# komahub-v1_2.net
KiCad netlist of a schematic drawn in EAGLE
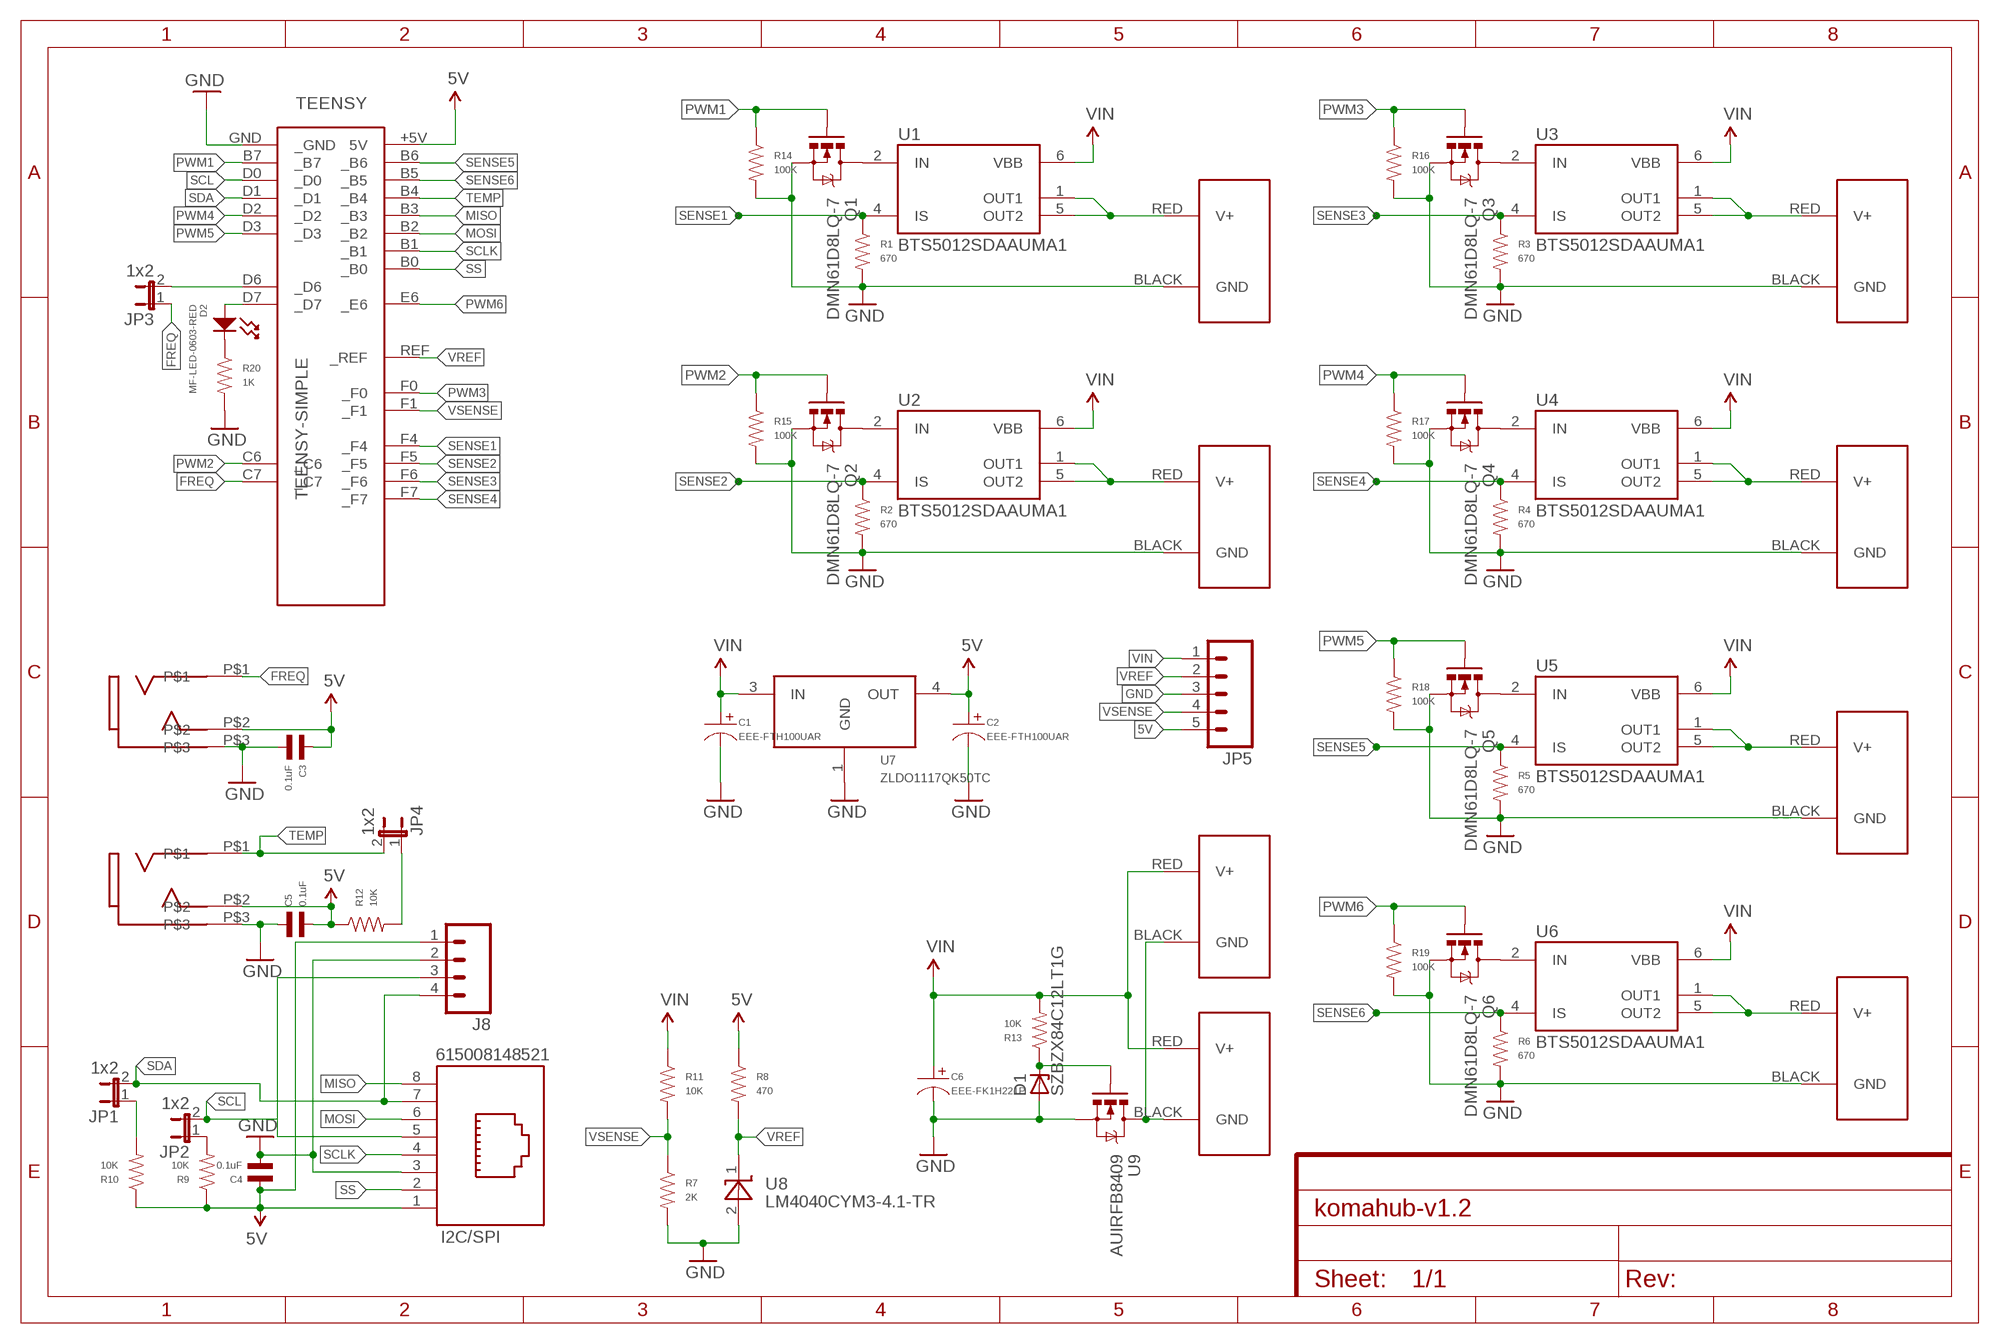
[diagram p0: schematic, sheet 1]

(export (version "E")
  (design (tool "Eeschema 10.0.6"))
  (components
    (comp (ref "C1")
      (value "EEE-FTH100UAR")
      (footprint "eagle-import:CP4MM")
      (fields (field (name "MPN") "MF-CAP-4MM-10uF"))
      (libsource (lib "eagle-import") (part "CAPACITOR_P_4MM"))
    )
    (comp (ref "C2")
      (value "EEE-FTH100UAR")
      (footprint "eagle-import:CP4MM")
      (fields (field (name "MPN") "MF-CAP-4MM-10uF"))
      (libsource (lib "eagle-import") (part "CAPACITOR_P_4MM"))
    )
    (comp (ref "C3")
      (value "0.1uF")
      (footprint "eagle-import:C0603")
      (libsource (lib "eagle-import") (part "CAPACITOR_NP_0603"))
    )
    (comp (ref "C4")
      (value "0.1uF")
      (footprint "eagle-import:C0603")
      (libsource (lib "eagle-import") (part "CAPACITOR_NP_0603"))
    )
    (comp (ref "C5")
      (value "0.1uF")
      (footprint "eagle-import:C0603")
      (libsource (lib "eagle-import") (part "CAPACITOR_NP_0603"))
    )
    (comp (ref "C6")
      (value "EEE-FK1H221P")
      (footprint "eagle-import:CP10MM")
      (fields (field (name "MPN") "EEE-FT1H221AP"))
      (libsource (lib "eagle-import") (part "CAPACITOR_P_10MM"))
    )
    (comp (ref "D1")
      (value "SZBZX84C12LT1G")
      (footprint "eagle-import:SOT23")
      (libsource (lib "eagle-import") (part "ZENER-DIODESOT23"))
    )
    (comp (ref "D2")
      (value "MF-LED-0603-RED")
      (footprint "eagle-import:LED0603")
      (fields (field (name "HOUSEPART") "YES"))
      (libsource (lib "eagle-import") (part "LED_SINGLE-0603-RED"))
    )
    (comp (ref "FREQ")
      (value "35RASMT2BHNTRX")
      (footprint "eagle-import:35RASMT2BHNTRX")
      (libsource (lib "eagle-import") (part "35RASMT2BHNTRX"))
    )
    (comp (ref "I2C/SPI")
      (value "615008148521")
      (footprint "eagle-import:615008148521")
      (libsource (lib "eagle-import") (part "615008148521"))
    )
    (comp (ref "J1")
      (value "POWERPOLE_POWER25A_HORIZONTAL_G11")
      (footprint "eagle-import:POWERPOLE_PAIR_25A_HORIZ_G11")
      (libsource (lib "eagle-import") (part "POWERPOLE_POWER25A_HORIZONTAL_G11"))
    )
    (comp (ref "J2")
      (value "POWERPOLE_POWER25A_HORIZONTAL_G11")
      (footprint "eagle-import:POWERPOLE_PAIR_25A_HORIZ_G11")
      (libsource (lib "eagle-import") (part "POWERPOLE_POWER25A_HORIZONTAL_G11"))
    )
    (comp (ref "J3")
      (value "POWERPOLE_POWER25A_HORIZONTAL_G12")
      (footprint "eagle-import:POWERPOLE_PAIR_25A_HORIZ_G12")
      (libsource (lib "eagle-import") (part "POWERPOLE_POWER25A_HORIZONTAL_G12"))
    )
    (comp (ref "J4")
      (value "POWERPOLE_POWER25A_HORIZONTAL_G12")
      (footprint "eagle-import:POWERPOLE_PAIR_25A_HORIZ_G12")
      (libsource (lib "eagle-import") (part "POWERPOLE_POWER25A_HORIZONTAL_G12"))
    )
    (comp (ref "J5")
      (value "POWERPOLE_POWER25A_HORIZONTAL_G12")
      (footprint "eagle-import:POWERPOLE_PAIR_25A_HORIZ_G12")
      (libsource (lib "eagle-import") (part "POWERPOLE_POWER25A_HORIZONTAL_G12"))
    )
    (comp (ref "J6")
      (value "POWERPOLE_POWER25A_HORIZONTAL_G11")
      (footprint "eagle-import:POWERPOLE_PAIR_25A_HORIZ_G11")
      (libsource (lib "eagle-import") (part "POWERPOLE_POWER25A_HORIZONTAL_G11"))
    )
    (comp (ref "J7")
      (value "POWERPOLE_POWER25A_HORIZONTAL_G11")
      (footprint "eagle-import:POWERPOLE_PAIR_25A_HORIZ_G11")
      (libsource (lib "eagle-import") (part "POWERPOLE_POWER25A_HORIZONTAL_G11"))
    )
    (comp (ref "J8")
      (value "M04PTH")
      (footprint "eagle-import:1X04")
      (libsource (lib "eagle-import") (part "M04PTH"))
    )
    (comp (ref "J9")
      (value "POWERPOLE_POWER25A_HORIZONTAL_G12")
      (footprint "eagle-import:POWERPOLE_PAIR_25A_HORIZ_G12")
      (libsource (lib "eagle-import") (part "POWERPOLE_POWER25A_HORIZONTAL_G12"))
    )
    (comp (ref "JP1")
      (value "1x2")
      (footprint "eagle-import:1X02")
      (libsource (lib "eagle-import") (part "JUMPER-2PTH"))
    )
    (comp (ref "JP2")
      (value "1x2")
      (footprint "eagle-import:1X02")
      (libsource (lib "eagle-import") (part "JUMPER-2PTH"))
    )
    (comp (ref "JP3")
      (value "1x2")
      (footprint "eagle-import:1X02")
      (libsource (lib "eagle-import") (part "JUMPER-2PTH"))
    )
    (comp (ref "JP4")
      (value "1x2")
      (footprint "eagle-import:1X02")
      (libsource (lib "eagle-import") (part "JUMPER-2PTH"))
    )
    (comp (ref "JP5")
      (value "M05PTH")
      (footprint "eagle-import:1X05")
      (libsource (lib "eagle-import") (part "M05PTH"))
    )
    (comp (ref "Q1")
      (value "DMN61D8LQ-7")
      (footprint "eagle-import:SOT23-3")
      (libsource (lib "eagle-import") (part "MOSFET-NCHANNELAO3404A"))
    )
    (comp (ref "Q2")
      (value "DMN61D8LQ-7")
      (footprint "eagle-import:SOT23-3")
      (libsource (lib "eagle-import") (part "MOSFET-NCHANNELAO3404A"))
    )
    (comp (ref "Q3")
      (value "DMN61D8LQ-7")
      (footprint "eagle-import:SOT23-3")
      (libsource (lib "eagle-import") (part "MOSFET-NCHANNELAO3404A"))
    )
    (comp (ref "Q4")
      (value "DMN61D8LQ-7")
      (footprint "eagle-import:SOT23-3")
      (libsource (lib "eagle-import") (part "MOSFET-NCHANNELAO3404A"))
    )
    (comp (ref "Q5")
      (value "DMN61D8LQ-7")
      (footprint "eagle-import:SOT23-3")
      (libsource (lib "eagle-import") (part "MOSFET-NCHANNELAO3404A"))
    )
    (comp (ref "Q6")
      (value "DMN61D8LQ-7")
      (footprint "eagle-import:SOT23-3")
      (libsource (lib "eagle-import") (part "MOSFET-NCHANNELAO3404A"))
    )
    (comp (ref "R1")
      (value "670")
      (footprint "eagle-import:R0603")
      (fields (field (name "MPN") "CR0603-FX-6800ELF"))
      (libsource (lib "eagle-import") (part "RESISTOR_0603"))
    )
    (comp (ref "R2")
      (value "670")
      (footprint "eagle-import:R0603")
      (fields (field (name "MPN") "CR0603-FX-6800ELF"))
      (libsource (lib "eagle-import") (part "RESISTOR_0603"))
    )
    (comp (ref "R3")
      (value "670")
      (footprint "eagle-import:R0603")
      (fields (field (name "MPN") "CR0603-FX-6800ELF"))
      (libsource (lib "eagle-import") (part "RESISTOR_0603"))
    )
    (comp (ref "R4")
      (value "670")
      (footprint "eagle-import:R0603")
      (fields (field (name "MPN") "CR0603-FX-6800ELF"))
      (libsource (lib "eagle-import") (part "RESISTOR_0603"))
    )
    (comp (ref "R5")
      (value "670")
      (footprint "eagle-import:R0603")
      (fields (field (name "MPN") "CR0603-FX-6800ELF"))
      (libsource (lib "eagle-import") (part "RESISTOR_0603"))
    )
    (comp (ref "R6")
      (value "670")
      (footprint "eagle-import:R0603")
      (fields (field (name "MPN") "CR0603-FX-6800ELF"))
      (libsource (lib "eagle-import") (part "RESISTOR_0603"))
    )
    (comp (ref "R7")
      (value "2K")
      (footprint "eagle-import:R0603")
      (fields (field (name "MPN") "MF-RES-0603-2K"))
      (libsource (lib "eagle-import") (part "RESISTOR_0603"))
    )
    (comp (ref "R8")
      (value "470")
      (footprint "eagle-import:R0603")
      (fields (field (name "MPN") "MF-RES-0603-470"))
      (libsource (lib "eagle-import") (part "RESISTOR_0603"))
    )
    (comp (ref "R9")
      (value "10K")
      (footprint "eagle-import:R0603")
      (fields (field (name "MPN") "MF-RES-0603-10K"))
      (libsource (lib "eagle-import") (part "RESISTOR_0603"))
    )
    (comp (ref "R10")
      (value "10K")
      (footprint "eagle-import:R0603")
      (fields (field (name "MPN") "MF-RES-0603-10K"))
      (libsource (lib "eagle-import") (part "RESISTOR_0603"))
    )
    (comp (ref "R11")
      (value "10K")
      (footprint "eagle-import:R0603")
      (fields (field (name "MPN") "MF-RES-0603-10K"))
      (libsource (lib "eagle-import") (part "RESISTOR_0603"))
    )
    (comp (ref "R12")
      (value "10K")
      (footprint "eagle-import:R0603")
      (fields (field (name "MPN") "MF-RES-0603-10K"))
      (libsource (lib "eagle-import") (part "RESISTOR_0603"))
    )
    (comp (ref "R13")
      (value "10K")
      (footprint "eagle-import:R0603")
      (fields (field (name "MPN") "MF-RES-0603-10K"))
      (libsource (lib "eagle-import") (part "RESISTOR_0603"))
    )
    (comp (ref "R14")
      (value "100K")
      (footprint "eagle-import:R0603")
      (fields (field (name "MPN") "MF-RES-0603-2K"))
      (libsource (lib "eagle-import") (part "RESISTOR_0603"))
    )
    (comp (ref "R15")
      (value "100K")
      (footprint "eagle-import:R0603")
      (fields (field (name "MPN") "MF-RES-0603-2K"))
      (libsource (lib "eagle-import") (part "RESISTOR_0603"))
    )
    (comp (ref "R16")
      (value "100K")
      (footprint "eagle-import:R0603")
      (fields (field (name "MPN") "MF-RES-0603-2K"))
      (libsource (lib "eagle-import") (part "RESISTOR_0603"))
    )
    (comp (ref "R17")
      (value "100K")
      (footprint "eagle-import:R0603")
      (fields (field (name "MPN") "MF-RES-0603-2K"))
      (libsource (lib "eagle-import") (part "RESISTOR_0603"))
    )
    (comp (ref "R18")
      (value "100K")
      (footprint "eagle-import:R0603")
      (fields (field (name "MPN") "MF-RES-0603-2K"))
      (libsource (lib "eagle-import") (part "RESISTOR_0603"))
    )
    (comp (ref "R19")
      (value "100K")
      (footprint "eagle-import:R0603")
      (fields (field (name "MPN") "MF-RES-0603-2K"))
      (libsource (lib "eagle-import") (part "RESISTOR_0603"))
    )
    (comp (ref "R20")
      (value "1K")
      (footprint "eagle-import:R0603")
      (libsource (lib "eagle-import") (part "RESISTOR_0603"))
    )
    (comp (ref "TEENSY")
      (value "TEENSY-SIMPLE")
      (footprint "eagle-import:TEENSY-SIMPLE")
      (libsource (lib "eagle-import") (part "TEENSY-SIMPLE"))
    )
    (comp (ref "TEMP")
      (value "35RASMT2BHNTRX")
      (footprint "eagle-import:35RASMT2BHNTRX")
      (libsource (lib "eagle-import") (part "35RASMT2BHNTRX"))
    )
    (comp (ref "U1")
      (value "BTS5012SDAAUMA1")
      (footprint "eagle-import:TO114P998X235-5_6N")
      (libsource (lib "eagle-import") (part "BTS5016SDA"))
    )
    (comp (ref "U2")
      (value "BTS5012SDAAUMA1")
      (footprint "eagle-import:TO114P998X235-5_6N")
      (libsource (lib "eagle-import") (part "BTS5016SDA"))
    )
    (comp (ref "U3")
      (value "BTS5012SDAAUMA1")
      (footprint "eagle-import:TO114P998X235-5_6N")
      (libsource (lib "eagle-import") (part "BTS5016SDA"))
    )
    (comp (ref "U4")
      (value "BTS5012SDAAUMA1")
      (footprint "eagle-import:TO114P998X235-5_6N")
      (libsource (lib "eagle-import") (part "BTS5016SDA"))
    )
    (comp (ref "U5")
      (value "BTS5012SDAAUMA1")
      (footprint "eagle-import:TO114P998X235-5_6N")
      (libsource (lib "eagle-import") (part "BTS5016SDA"))
    )
    (comp (ref "U6")
      (value "BTS5012SDAAUMA1")
      (footprint "eagle-import:TO114P998X235-5_6N")
      (libsource (lib "eagle-import") (part "BTS5016SDA"))
    )
    (comp (ref "U7")
      (value "ZLDO1117QK50TC")
      (footprint "eagle-import:DPAK")
      (libsource (lib "eagle-import") (part "NCV1117"))
    )
    (comp (ref "U8")
      (value "LM4040CYM3-4.1-TR")
      (footprint "eagle-import:SOT-23")
      (libsource (lib "eagle-import") (part "LM4040CYM3-2.5"))
    )
    (comp (ref "U9")
      (value "AUIRFB8409")
      (footprint "eagle-import:TO220AV")
      (libsource (lib "eagle-import") (part "AUIRFB8409"))
    )
  )
  (nets
    (net (code "1") (name "5V") (class "Default")
      (node (ref "C2") (pin "P$1") (pinfunction "P$1_P$1") (pintype "passive"))
      (node (ref "C3") (pin "P$1") (pinfunction "P$1_P$1") (pintype "passive"))
      (node (ref "C4") (pin "P$1") (pinfunction "P$1_P$1") (pintype "passive"))
      (node (ref "C5") (pin "P$2") (pinfunction "P$2_P$2") (pintype "passive"))
      (node (ref "FREQ") (pin "P$2") (pinfunction "P$2_P$2") (pintype "bidirectional"))
      (node (ref "I2C/SPI") (pin "1") (pinfunction "8_1") (pintype "passive"))
      (node (ref "J8") (pin "1") (pinfunction "1_1") (pintype "passive"))
      (node (ref "JP5") (pin "5") (pinfunction "5_5") (pintype "passive"))
      (node (ref "R10") (pin "P$1") (pinfunction "P$1_P$1") (pintype "passive"))
      (node (ref "R12") (pin "P$1") (pinfunction "P$1_P$1") (pintype "passive"))
      (node (ref "R8") (pin "P$1") (pinfunction "P$1_P$1") (pintype "passive"))
      (node (ref "R9") (pin "P$1") (pinfunction "P$1_P$1") (pintype "passive"))
      (node (ref "TEENSY") (pin "+5V") (pinfunction "5V_+5V") (pintype "bidirectional"))
      (node (ref "TEMP") (pin "P$2") (pinfunction "P$2_P$2") (pintype "bidirectional"))
      (node (ref "U7") (pin "4") (pinfunction "OUT_4") (pintype "bidirectional"))
    )
    (net (code "2") (name "FREQ") (class "Default")
      (node (ref "FREQ") (pin "P$1") (pinfunction "P$1_P$1") (pintype "bidirectional"))
      (node (ref "JP3") (pin "1") (pinfunction "1_1") (pintype "passive"))
      (node (ref "TEENSY") (pin "C7") (pinfunction "_C7_C7") (pintype "bidirectional"))
    )
    (net (code "3") (name "GND") (class "Default")
      (node (ref "C1") (pin "P$2") (pinfunction "P$2_P$2") (pintype "passive"))
      (node (ref "C2") (pin "P$2") (pinfunction "P$2_P$2") (pintype "passive"))
      (node (ref "C3") (pin "P$2") (pinfunction "P$2_P$2") (pintype "passive"))
      (node (ref "C4") (pin "P$2") (pinfunction "P$2_P$2") (pintype "passive"))
      (node (ref "C5") (pin "P$1") (pinfunction "P$1_P$1") (pintype "passive"))
      (node (ref "C6") (pin "P$2") (pinfunction "P$2_P$2") (pintype "passive"))
      (node (ref "D1") (pin "1") (pinfunction "A_1") (pintype "passive"))
      (node (ref "FREQ") (pin "P$3") (pinfunction "P$3_P$3") (pintype "bidirectional"))
      (node (ref "I2C/SPI") (pin "3") (pinfunction "6_3") (pintype "passive"))
      (node (ref "J1") (pin "BLACK") (pinfunction "GND_BLACK") (pintype "power_in"))
      (node (ref "J2") (pin "BLACK") (pinfunction "GND_BLACK") (pintype "power_in"))
      (node (ref "J3") (pin "BLACK") (pinfunction "GND_BLACK") (pintype "power_in"))
      (node (ref "J5") (pin "BLACK") (pinfunction "GND_BLACK") (pintype "power_in"))
      (node (ref "J7") (pin "BLACK") (pinfunction "GND_BLACK") (pintype "power_in"))
      (node (ref "J8") (pin "2") (pinfunction "2_2") (pintype "passive"))
      (node (ref "J9") (pin "BLACK") (pinfunction "GND_BLACK") (pintype "power_in"))
      (node (ref "JP5") (pin "3") (pinfunction "3_3") (pintype "passive"))
      (node (ref "Q1") (pin "2") (pinfunction "S_2") (pintype "passive"))
      (node (ref "Q2") (pin "2") (pinfunction "S_2") (pintype "passive"))
      (node (ref "Q3") (pin "2") (pinfunction "S_2") (pintype "passive"))
      (node (ref "Q4") (pin "2") (pinfunction "S_2") (pintype "passive"))
      (node (ref "Q5") (pin "2") (pinfunction "S_2") (pintype "passive"))
      (node (ref "Q6") (pin "2") (pinfunction "S_2") (pintype "passive"))
      (node (ref "R1") (pin "P$2") (pinfunction "P$2_P$2") (pintype "passive"))
      (node (ref "R14") (pin "P$2") (pinfunction "P$2_P$2") (pintype "passive"))
      (node (ref "R15") (pin "P$2") (pinfunction "P$2_P$2") (pintype "passive"))
      (node (ref "R16") (pin "P$2") (pinfunction "P$2_P$2") (pintype "passive"))
      (node (ref "R17") (pin "P$2") (pinfunction "P$2_P$2") (pintype "passive"))
      (node (ref "R18") (pin "P$2") (pinfunction "P$2_P$2") (pintype "passive"))
      (node (ref "R19") (pin "P$2") (pinfunction "P$2_P$2") (pintype "passive"))
      (node (ref "R2") (pin "P$2") (pinfunction "P$2_P$2") (pintype "passive"))
      (node (ref "R20") (pin "P$2") (pinfunction "P$2_P$2") (pintype "passive"))
      (node (ref "R3") (pin "P$2") (pinfunction "P$2_P$2") (pintype "passive"))
      (node (ref "R4") (pin "P$2") (pinfunction "P$2_P$2") (pintype "passive"))
      (node (ref "R5") (pin "P$2") (pinfunction "P$2_P$2") (pintype "passive"))
      (node (ref "R6") (pin "P$2") (pinfunction "P$2_P$2") (pintype "passive"))
      (node (ref "R7") (pin "P$2") (pinfunction "P$2_P$2") (pintype "passive"))
      (node (ref "TEENSY") (pin "GND") (pinfunction "_GND_GND") (pintype "bidirectional"))
      (node (ref "TEMP") (pin "P$3") (pinfunction "P$3_P$3") (pintype "bidirectional"))
      (node (ref "U7") (pin "1") (pinfunction "GND_1") (pintype "bidirectional"))
      (node (ref "U8") (pin "2") (pinfunction "A_2") (pintype "output"))
      (node (ref "U9") (pin "3") (pinfunction "S_3") (pintype "passive"))
    )
    (net (code "4") (name "MISO") (class "Default")
      (node (ref "I2C/SPI") (pin "8") (pinfunction "1_8") (pintype "passive"))
      (node (ref "TEENSY") (pin "B3") (pinfunction "_B3_B3") (pintype "bidirectional"))
    )
    (net (code "5") (name "MOSI") (class "Default")
      (node (ref "I2C/SPI") (pin "6") (pinfunction "3_6") (pintype "passive"))
      (node (ref "TEENSY") (pin "B2") (pinfunction "_B2_B2") (pintype "bidirectional"))
    )
    (net (code "6") (name "Net-(D1-C)") (class "Default")
      (node (ref "D1") (pin "3") (pinfunction "C_3") (pintype "passive"))
      (node (ref "R13") (pin "P$1") (pinfunction "P$1_P$1") (pintype "passive"))
      (node (ref "U9") (pin "1") (pinfunction "G_1") (pintype "passive"))
    )
    (net (code "7") (name "Net-(D2-PadCATHODE)") (class "Default")
      (node (ref "D2") (pin "CATHODE") (pinfunction "CATHODE_CATHODE") (pintype "power_in"))
      (node (ref "R20") (pin "P$1") (pinfunction "P$1_P$1") (pintype "passive"))
    )
    (net (code "8") (name "Net-(J1-V+)") (class "Default")
      (node (ref "J1") (pin "RED") (pinfunction "V+_RED") (pintype "power_in"))
      (node (ref "U3") (pin "1") (pinfunction "OUT1_1") (pintype "output"))
      (node (ref "U3") (pin "5") (pinfunction "OUT2_5") (pintype "output"))
    )
    (net (code "9") (name "Net-(J2-V+)") (class "Default")
      (node (ref "J2") (pin "RED") (pinfunction "V+_RED") (pintype "power_in"))
      (node (ref "U1") (pin "1") (pinfunction "OUT1_1") (pintype "output"))
      (node (ref "U1") (pin "5") (pinfunction "OUT2_5") (pintype "output"))
    )
    (net (code "10") (name "Net-(J3-V+)") (class "Default")
      (node (ref "J3") (pin "RED") (pinfunction "V+_RED") (pintype "power_in"))
      (node (ref "U2") (pin "1") (pinfunction "OUT1_1") (pintype "output"))
      (node (ref "U2") (pin "5") (pinfunction "OUT2_5") (pintype "output"))
    )
    (net (code "11") (name "Net-(J4-GND)") (class "Default")
      (node (ref "J4") (pin "BLACK") (pinfunction "GND_BLACK") (pintype "power_in"))
      (node (ref "J6") (pin "BLACK") (pinfunction "GND_BLACK") (pintype "power_in"))
      (node (ref "U9") (pin "2") (pinfunction "D_2") (pintype "passive"))
    )
    (net (code "12") (name "Net-(J5-V+)") (class "Default")
      (node (ref "J5") (pin "RED") (pinfunction "V+_RED") (pintype "power_in"))
      (node (ref "U4") (pin "1") (pinfunction "OUT1_1") (pintype "output"))
      (node (ref "U4") (pin "5") (pinfunction "OUT2_5") (pintype "output"))
    )
    (net (code "13") (name "Net-(J7-V+)") (class "Default")
      (node (ref "J7") (pin "RED") (pinfunction "V+_RED") (pintype "power_in"))
      (node (ref "U5") (pin "1") (pinfunction "OUT1_1") (pintype "output"))
      (node (ref "U5") (pin "5") (pinfunction "OUT2_5") (pintype "output"))
    )
    (net (code "14") (name "Net-(J9-V+)") (class "Default")
      (node (ref "J9") (pin "RED") (pinfunction "V+_RED") (pintype "power_in"))
      (node (ref "U6") (pin "1") (pinfunction "OUT1_1") (pintype "output"))
      (node (ref "U6") (pin "5") (pinfunction "OUT2_5") (pintype "output"))
    )
    (net (code "15") (name "Net-(JP1-Pad1)") (class "Default")
      (node (ref "JP1") (pin "1") (pinfunction "1_1") (pintype "passive"))
      (node (ref "R10") (pin "P$2") (pinfunction "P$2_P$2") (pintype "passive"))
    )
    (net (code "16") (name "Net-(JP2-Pad1)") (class "Default")
      (node (ref "JP2") (pin "1") (pinfunction "1_1") (pintype "passive"))
      (node (ref "R9") (pin "P$2") (pinfunction "P$2_P$2") (pintype "passive"))
    )
    (net (code "17") (name "Net-(JP4-Pad1)") (class "Default")
      (node (ref "JP4") (pin "1") (pinfunction "1_1") (pintype "passive"))
      (node (ref "R12") (pin "P$2") (pinfunction "P$2_P$2") (pintype "passive"))
    )
    (net (code "18") (name "Net-(Q1-D)") (class "Default")
      (node (ref "Q1") (pin "3") (pinfunction "D_3") (pintype "passive"))
      (node (ref "U1") (pin "2") (pinfunction "IN_2") (pintype "input"))
    )
    (net (code "19") (name "Net-(Q2-D)") (class "Default")
      (node (ref "Q2") (pin "3") (pinfunction "D_3") (pintype "passive"))
      (node (ref "U2") (pin "2") (pinfunction "IN_2") (pintype "input"))
    )
    (net (code "20") (name "Net-(Q3-D)") (class "Default")
      (node (ref "Q3") (pin "3") (pinfunction "D_3") (pintype "passive"))
      (node (ref "U3") (pin "2") (pinfunction "IN_2") (pintype "input"))
    )
    (net (code "21") (name "Net-(Q4-D)") (class "Default")
      (node (ref "Q4") (pin "3") (pinfunction "D_3") (pintype "passive"))
      (node (ref "U4") (pin "2") (pinfunction "IN_2") (pintype "input"))
    )
    (net (code "22") (name "Net-(Q5-D)") (class "Default")
      (node (ref "Q5") (pin "3") (pinfunction "D_3") (pintype "passive"))
      (node (ref "U5") (pin "2") (pinfunction "IN_2") (pintype "input"))
    )
    (net (code "23") (name "Net-(Q6-D)") (class "Default")
      (node (ref "Q6") (pin "3") (pinfunction "D_3") (pintype "passive"))
      (node (ref "U6") (pin "2") (pinfunction "IN_2") (pintype "input"))
    )
    (net (code "24") (name "Net-(TEENSY-_D6)") (class "Default")
      (node (ref "JP3") (pin "2") (pinfunction "2_2") (pintype "passive"))
      (node (ref "TEENSY") (pin "D6") (pinfunction "_D6_D6") (pintype "bidirectional"))
    )
    (net (code "25") (name "Net-(TEENSY-_D7)") (class "Default")
      (node (ref "D2") (pin "ANODE") (pinfunction "ANODE_ANODE") (pintype "power_in"))
      (node (ref "TEENSY") (pin "D7") (pinfunction "_D7_D7") (pintype "bidirectional"))
    )
    (net (code "26") (name "PWM1") (class "Default")
      (node (ref "Q1") (pin "1") (pinfunction "G_1") (pintype "passive"))
      (node (ref "R14") (pin "P$1") (pinfunction "P$1_P$1") (pintype "passive"))
      (node (ref "TEENSY") (pin "B7") (pinfunction "_B7_B7") (pintype "bidirectional"))
    )
    (net (code "27") (name "PWM2") (class "Default")
      (node (ref "Q2") (pin "1") (pinfunction "G_1") (pintype "passive"))
      (node (ref "R15") (pin "P$1") (pinfunction "P$1_P$1") (pintype "passive"))
      (node (ref "TEENSY") (pin "C6") (pinfunction "_C6_C6") (pintype "bidirectional"))
    )
    (net (code "28") (name "PWM3") (class "Default")
      (node (ref "Q3") (pin "1") (pinfunction "G_1") (pintype "passive"))
      (node (ref "R16") (pin "P$1") (pinfunction "P$1_P$1") (pintype "passive"))
      (node (ref "TEENSY") (pin "F0") (pinfunction "_F0_F0") (pintype "bidirectional"))
    )
    (net (code "29") (name "PWM4") (class "Default")
      (node (ref "Q4") (pin "1") (pinfunction "G_1") (pintype "passive"))
      (node (ref "R17") (pin "P$1") (pinfunction "P$1_P$1") (pintype "passive"))
      (node (ref "TEENSY") (pin "D2") (pinfunction "_D2_D2") (pintype "bidirectional"))
    )
    (net (code "30") (name "PWM5") (class "Default")
      (node (ref "Q5") (pin "1") (pinfunction "G_1") (pintype "passive"))
      (node (ref "R18") (pin "P$1") (pinfunction "P$1_P$1") (pintype "passive"))
      (node (ref "TEENSY") (pin "D3") (pinfunction "_D3_D3") (pintype "bidirectional"))
    )
    (net (code "31") (name "PWM6") (class "Default")
      (node (ref "Q6") (pin "1") (pinfunction "G_1") (pintype "passive"))
      (node (ref "R19") (pin "P$1") (pinfunction "P$1_P$1") (pintype "passive"))
      (node (ref "TEENSY") (pin "E6") (pinfunction "_E6_E6") (pintype "bidirectional"))
    )
    (net (code "32") (name "SCL") (class "Default")
      (node (ref "I2C/SPI") (pin "5") (pinfunction "4_5") (pintype "passive"))
      (node (ref "J8") (pin "3") (pinfunction "3_3") (pintype "passive"))
      (node (ref "JP2") (pin "2") (pinfunction "2_2") (pintype "passive"))
      (node (ref "TEENSY") (pin "D0") (pinfunction "_D0_D0") (pintype "bidirectional"))
    )
    (net (code "33") (name "SCLK") (class "Default")
      (node (ref "I2C/SPI") (pin "4") (pinfunction "5_4") (pintype "passive"))
      (node (ref "TEENSY") (pin "B1") (pinfunction "_B1_B1") (pintype "bidirectional"))
    )
    (net (code "34") (name "SDA") (class "Default")
      (node (ref "I2C/SPI") (pin "7") (pinfunction "2_7") (pintype "passive"))
      (node (ref "J8") (pin "4") (pinfunction "4_4") (pintype "passive"))
      (node (ref "JP1") (pin "2") (pinfunction "2_2") (pintype "passive"))
      (node (ref "TEENSY") (pin "D1") (pinfunction "_D1_D1") (pintype "bidirectional"))
    )
    (net (code "35") (name "SENSE1") (class "Default")
      (node (ref "R1") (pin "P$1") (pinfunction "P$1_P$1") (pintype "passive"))
      (node (ref "TEENSY") (pin "F4") (pinfunction "_F4_F4") (pintype "bidirectional"))
      (node (ref "U1") (pin "4") (pinfunction "IS_4") (pintype "output"))
    )
    (net (code "36") (name "SENSE2") (class "Default")
      (node (ref "R2") (pin "P$1") (pinfunction "P$1_P$1") (pintype "passive"))
      (node (ref "TEENSY") (pin "F5") (pinfunction "_F5_F5") (pintype "bidirectional"))
      (node (ref "U2") (pin "4") (pinfunction "IS_4") (pintype "output"))
    )
    (net (code "37") (name "SENSE3") (class "Default")
      (node (ref "R3") (pin "P$1") (pinfunction "P$1_P$1") (pintype "passive"))
      (node (ref "TEENSY") (pin "F6") (pinfunction "_F6_F6") (pintype "bidirectional"))
      (node (ref "U3") (pin "4") (pinfunction "IS_4") (pintype "output"))
    )
    (net (code "38") (name "SENSE4") (class "Default")
      (node (ref "R4") (pin "P$1") (pinfunction "P$1_P$1") (pintype "passive"))
      (node (ref "TEENSY") (pin "F7") (pinfunction "_F7_F7") (pintype "bidirectional"))
      (node (ref "U4") (pin "4") (pinfunction "IS_4") (pintype "output"))
    )
    (net (code "39") (name "SENSE5") (class "Default")
      (node (ref "R5") (pin "P$1") (pinfunction "P$1_P$1") (pintype "passive"))
      (node (ref "TEENSY") (pin "B6") (pinfunction "_B6_B6") (pintype "bidirectional"))
      (node (ref "U5") (pin "4") (pinfunction "IS_4") (pintype "output"))
    )
    (net (code "40") (name "SENSE6") (class "Default")
      (node (ref "R6") (pin "P$1") (pinfunction "P$1_P$1") (pintype "passive"))
      (node (ref "TEENSY") (pin "B5") (pinfunction "_B5_B5") (pintype "bidirectional"))
      (node (ref "U6") (pin "4") (pinfunction "IS_4") (pintype "output"))
    )
    (net (code "41") (name "SS") (class "Default")
      (node (ref "I2C/SPI") (pin "2") (pinfunction "7_2") (pintype "passive"))
      (node (ref "TEENSY") (pin "B0") (pinfunction "_B0_B0") (pintype "bidirectional"))
    )
    (net (code "42") (name "TEMP") (class "Default")
      (node (ref "JP4") (pin "2") (pinfunction "2_2") (pintype "passive"))
      (node (ref "TEENSY") (pin "B4") (pinfunction "_B4_B4") (pintype "bidirectional"))
      (node (ref "TEMP") (pin "P$1") (pinfunction "P$1_P$1") (pintype "bidirectional"))
    )
    (net (code "43") (name "VIN") (class "Default")
      (node (ref "C1") (pin "P$1") (pinfunction "P$1_P$1") (pintype "passive"))
      (node (ref "C6") (pin "P$1") (pinfunction "P$1_P$1") (pintype "passive"))
      (node (ref "J4") (pin "RED") (pinfunction "V+_RED") (pintype "power_in"))
      (node (ref "J6") (pin "RED") (pinfunction "V+_RED") (pintype "power_in"))
      (node (ref "JP5") (pin "1") (pinfunction "1_1") (pintype "passive"))
      (node (ref "R11") (pin "P$1") (pinfunction "P$1_P$1") (pintype "passive"))
      (node (ref "R13") (pin "P$2") (pinfunction "P$2_P$2") (pintype "passive"))
      (node (ref "U1") (pin "6") (pinfunction "VBB_6") (pintype "power_in"))
      (node (ref "U2") (pin "6") (pinfunction "VBB_6") (pintype "power_in"))
      (node (ref "U3") (pin "6") (pinfunction "VBB_6") (pintype "power_in"))
      (node (ref "U4") (pin "6") (pinfunction "VBB_6") (pintype "power_in"))
      (node (ref "U5") (pin "6") (pinfunction "VBB_6") (pintype "power_in"))
      (node (ref "U6") (pin "6") (pinfunction "VBB_6") (pintype "power_in"))
      (node (ref "U7") (pin "3") (pinfunction "IN_3") (pintype "bidirectional"))
    )
    (net (code "44") (name "VREF") (class "Default")
      (node (ref "JP5") (pin "2") (pinfunction "2_2") (pintype "passive"))
      (node (ref "R8") (pin "P$2") (pinfunction "P$2_P$2") (pintype "passive"))
      (node (ref "TEENSY") (pin "REF") (pinfunction "_REF_REF") (pintype "bidirectional"))
      (node (ref "U8") (pin "1") (pinfunction "C_1") (pintype "input"))
    )
    (net (code "45") (name "VSENSE") (class "Default")
      (node (ref "JP5") (pin "4") (pinfunction "4_4") (pintype "passive"))
      (node (ref "R11") (pin "P$2") (pinfunction "P$2_P$2") (pintype "passive"))
      (node (ref "R7") (pin "P$1") (pinfunction "P$1_P$1") (pintype "passive"))
      (node (ref "TEENSY") (pin "F1") (pinfunction "_F1_F1") (pintype "bidirectional"))
    )
  )
)
